# M502A.net
KiCad netlist of a schematic drawn in EAGLE
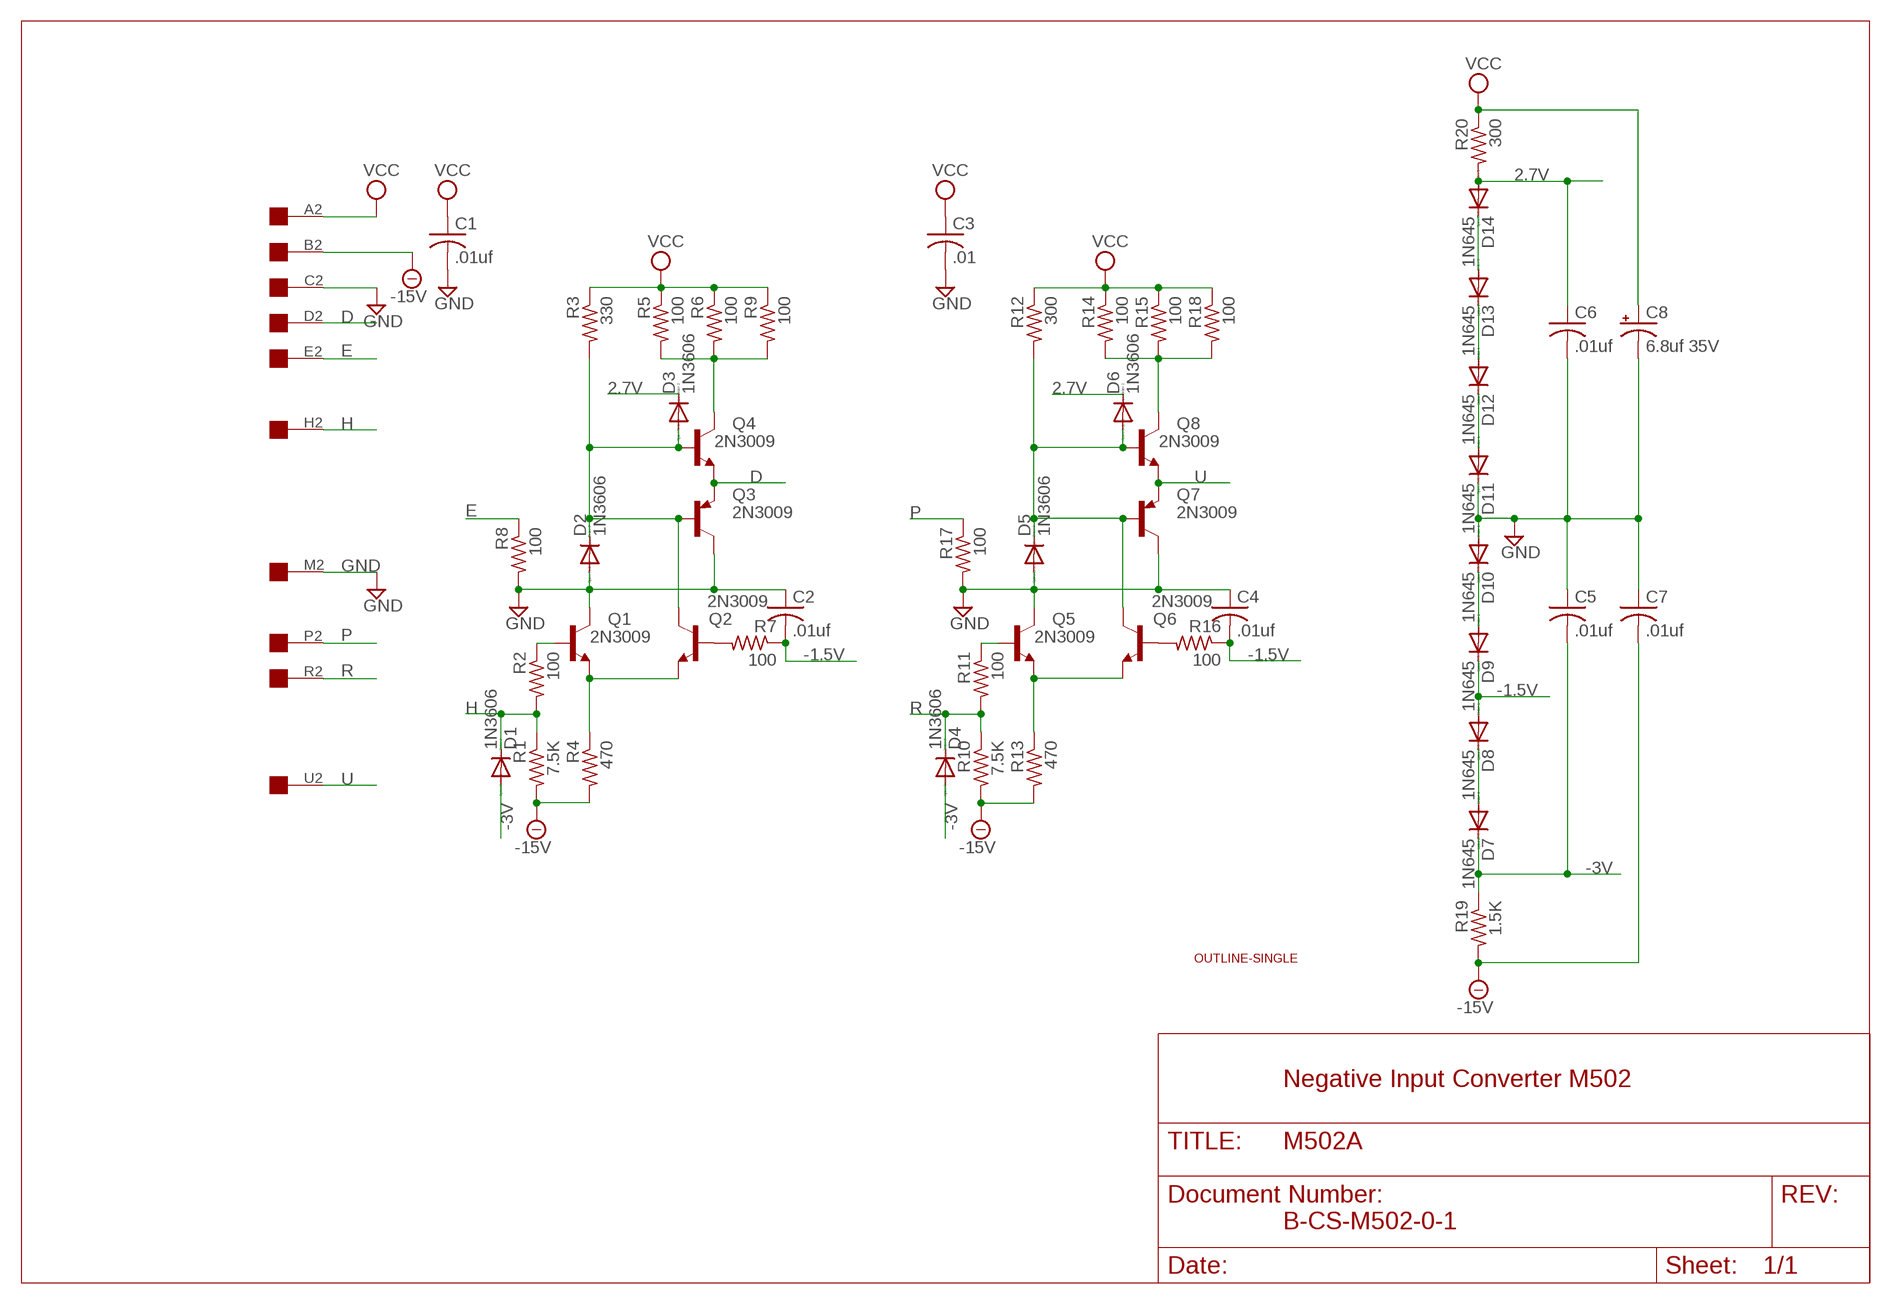
[diagram p0: schematic, sheet 1]

(export (version "E")
  (design (tool "Eeschema 10.0.6"))
  (components
    (comp (ref "C1")
      (value ".01uf")
      (footprint "eagle-import:C050-025X075")
      (libsource (lib "eagle-import") (part "C-US050-025X075"))
    )
    (comp (ref "C2")
      (value ".01uf")
      (footprint "eagle-import:C050-025X075")
      (libsource (lib "eagle-import") (part "C-US050-025X075"))
    )
    (comp (ref "C3")
      (value ".01")
      (footprint "eagle-import:C050-025X075")
      (libsource (lib "eagle-import") (part "C-US050-025X075"))
    )
    (comp (ref "C4")
      (value ".01uf")
      (footprint "eagle-import:C050-025X075")
      (libsource (lib "eagle-import") (part "C-US050-025X075"))
    )
    (comp (ref "C5")
      (value ".01uf")
      (footprint "eagle-import:C050-025X075")
      (libsource (lib "eagle-import") (part "C-US050-025X075"))
    )
    (comp (ref "C6")
      (value ".01uf")
      (footprint "eagle-import:C050-025X075")
      (libsource (lib "eagle-import") (part "C-US050-025X075"))
    )
    (comp (ref "C7")
      (value ".01uf")
      (footprint "eagle-import:C050-025X075")
      (libsource (lib "eagle-import") (part "C-US050-025X075"))
    )
    (comp (ref "C8")
      (value "6.8uf 35V")
      (footprint "eagle-import:E15-5")
      (libsource (lib "eagle-import") (part "CPOL-USE15-5AXIAL"))
    )
    (comp (ref "D1")
      (value "1N3606")
      (footprint "eagle-import:DO41-10")
      (libsource (lib "eagle-import") (part "1N4004"))
    )
    (comp (ref "D2")
      (value "1N3606")
      (footprint "eagle-import:DO41-10")
      (libsource (lib "eagle-import") (part "1N4004"))
    )
    (comp (ref "D3")
      (value "1N3606")
      (footprint "eagle-import:DO41-10")
      (libsource (lib "eagle-import") (part "1N4004"))
    )
    (comp (ref "D4")
      (value "1N3606")
      (footprint "eagle-import:DO41-10")
      (libsource (lib "eagle-import") (part "1N4004"))
    )
    (comp (ref "D5")
      (value "1N3606")
      (footprint "eagle-import:DO41-10")
      (libsource (lib "eagle-import") (part "1N4004"))
    )
    (comp (ref "D6")
      (value "1N3606")
      (footprint "eagle-import:DO41-10")
      (libsource (lib "eagle-import") (part "1N4004"))
    )
    (comp (ref "D7")
      (value "1N645")
      (footprint "eagle-import:DO41-10")
      (libsource (lib "eagle-import") (part "1N4004"))
    )
    (comp (ref "D8")
      (value "1N645")
      (footprint "eagle-import:DO41-10")
      (libsource (lib "eagle-import") (part "1N4004"))
    )
    (comp (ref "D9")
      (value "1N645")
      (footprint "eagle-import:DO41-10")
      (libsource (lib "eagle-import") (part "1N4004"))
    )
    (comp (ref "D10")
      (value "1N645")
      (footprint "eagle-import:DO41-10")
      (libsource (lib "eagle-import") (part "1N4004"))
    )
    (comp (ref "D11")
      (value "1N645")
      (footprint "eagle-import:DO41-10")
      (libsource (lib "eagle-import") (part "1N4004"))
    )
    (comp (ref "D12")
      (value "1N645")
      (footprint "eagle-import:DO41-10")
      (libsource (lib "eagle-import") (part "1N4004"))
    )
    (comp (ref "D13")
      (value "1N645")
      (footprint "eagle-import:DO41-10")
      (libsource (lib "eagle-import") (part "1N4004"))
    )
    (comp (ref "D14")
      (value "1N645")
      (footprint "eagle-import:DO41-10")
      (libsource (lib "eagle-import") (part "1N4004"))
    )
    (comp (ref "Q1")
      (value "2N3009")
      (footprint "eagle-import:TO39")
      (libsource (lib "eagle-import") (part "2N1711"))
    )
    (comp (ref "Q2")
      (value "2N3009")
      (footprint "eagle-import:TO39")
      (libsource (lib "eagle-import") (part "2N1711"))
    )
    (comp (ref "Q3")
      (value "2N3009")
      (footprint "eagle-import:TO39")
      (libsource (lib "eagle-import") (part "2N5415"))
    )
    (comp (ref "Q4")
      (value "2N3009")
      (footprint "eagle-import:TO39")
      (libsource (lib "eagle-import") (part "2N1711"))
    )
    (comp (ref "Q5")
      (value "2N3009")
      (footprint "eagle-import:TO39")
      (libsource (lib "eagle-import") (part "2N1711"))
    )
    (comp (ref "Q6")
      (value "2N3009")
      (footprint "eagle-import:TO39")
      (libsource (lib "eagle-import") (part "2N1711"))
    )
    (comp (ref "Q7")
      (value "2N3009")
      (footprint "eagle-import:TO39")
      (libsource (lib "eagle-import") (part "2N5415"))
    )
    (comp (ref "Q8")
      (value "2N3009")
      (footprint "eagle-import:TO39")
      (libsource (lib "eagle-import") (part "2N1711"))
    )
    (comp (ref "R1")
      (value "7.5K")
      (footprint "eagle-import:0207_10")
      (libsource (lib "eagle-import") (part "R-US_0207/10"))
    )
    (comp (ref "R2")
      (value "100")
      (footprint "eagle-import:0207_10")
      (libsource (lib "eagle-import") (part "R-US_0207/10"))
    )
    (comp (ref "R3")
      (value "330")
      (footprint "eagle-import:0207_10")
      (libsource (lib "eagle-import") (part "R-US_0207/10"))
    )
    (comp (ref "R4")
      (value "470")
      (footprint "eagle-import:0207_10")
      (libsource (lib "eagle-import") (part "R-US_0207/10"))
    )
    (comp (ref "R5")
      (value "100")
      (footprint "eagle-import:0207_10")
      (libsource (lib "eagle-import") (part "R-US_0207/10"))
    )
    (comp (ref "R6")
      (value "100")
      (footprint "eagle-import:0207_10")
      (libsource (lib "eagle-import") (part "R-US_0207/10"))
    )
    (comp (ref "R7")
      (value "100")
      (footprint "eagle-import:0207_10")
      (libsource (lib "eagle-import") (part "R-US_0207/10"))
    )
    (comp (ref "R8")
      (value "100")
      (footprint "eagle-import:0207_10")
      (libsource (lib "eagle-import") (part "R-US_0207/10"))
    )
    (comp (ref "R9")
      (value "100")
      (footprint "eagle-import:0207_10")
      (libsource (lib "eagle-import") (part "R-US_0207/10"))
    )
    (comp (ref "R10")
      (value "7.5K")
      (footprint "eagle-import:0207_10")
      (libsource (lib "eagle-import") (part "R-US_0207/10"))
    )
    (comp (ref "R11")
      (value "100")
      (footprint "eagle-import:0207_10")
      (libsource (lib "eagle-import") (part "R-US_0207/10"))
    )
    (comp (ref "R12")
      (value "300")
      (footprint "eagle-import:0207_10")
      (libsource (lib "eagle-import") (part "R-US_0207/10"))
    )
    (comp (ref "R13")
      (value "470")
      (footprint "eagle-import:0207_10")
      (libsource (lib "eagle-import") (part "R-US_0207/10"))
    )
    (comp (ref "R14")
      (value "100")
      (footprint "eagle-import:0207_10")
      (libsource (lib "eagle-import") (part "R-US_0207/10"))
    )
    (comp (ref "R15")
      (value "100")
      (footprint "eagle-import:0207_10")
      (libsource (lib "eagle-import") (part "R-US_0207/10"))
    )
    (comp (ref "R16")
      (value "100")
      (footprint "eagle-import:0207_10")
      (libsource (lib "eagle-import") (part "R-US_0207/10"))
    )
    (comp (ref "R17")
      (value "100")
      (footprint "eagle-import:0207_10")
      (libsource (lib "eagle-import") (part "R-US_0207/10"))
    )
    (comp (ref "R18")
      (value "100")
      (footprint "eagle-import:0207_10")
      (libsource (lib "eagle-import") (part "R-US_0207/10"))
    )
    (comp (ref "R19")
      (value "1.5K")
      (footprint "eagle-import:0207_10")
      (libsource (lib "eagle-import") (part "R-US_0207/10"))
    )
    (comp (ref "R20")
      (value "300")
      (footprint "eagle-import:0207_10")
      (libsource (lib "eagle-import") (part "R-US_0207/10"))
    )
    (comp (ref "U$1")
      (value "EDGE-1")
      (footprint "eagle-import:EDGE-CON1")
      (libsource (lib "eagle-import") (part "EDGE-1"))
    )
    (comp (ref "U$2")
      (value "OUTLINE-SINGLE")
      (footprint "eagle-import:SINGLE")
      (libsource (lib "eagle-import") (part "OUTLINE-SINGLE"))
    )
  )
  (nets
    (net (code "1") (name "-15V") (class "Default")
      (node (ref "C7") (pin "2") (pinfunction "2_2") (pintype "passive"))
      (node (ref "R1") (pin "2") (pinfunction "2_2") (pintype "passive"))
      (node (ref "R10") (pin "2") (pinfunction "2_2") (pintype "passive"))
      (node (ref "R13") (pin "2") (pinfunction "2_2") (pintype "passive"))
      (node (ref "R19") (pin "2") (pinfunction "2_2") (pintype "passive"))
      (node (ref "R4") (pin "2") (pinfunction "2_2") (pintype "passive"))
      (node (ref "U$1") (pin "B2") (pinfunction "1_B2") (pintype "bidirectional"))
    )
    (net (code "2") (name "/-1.5V") (class "Default")
      (node (ref "C2") (pin "2") (pinfunction "2_2") (pintype "passive"))
      (node (ref "C4") (pin "2") (pinfunction "2_2") (pintype "passive"))
      (node (ref "D8") (pin "A") (pinfunction "A_A") (pintype "passive"))
      (node (ref "D9") (pin "C") (pinfunction "C_C") (pintype "passive"))
      (node (ref "R16") (pin "1") (pinfunction "1_1") (pintype "passive"))
      (node (ref "R7") (pin "1") (pinfunction "1_1") (pintype "passive"))
    )
    (net (code "3") (name "/-3V") (class "Default")
      (node (ref "C5") (pin "2") (pinfunction "2_2") (pintype "passive"))
      (node (ref "D1") (pin "A") (pinfunction "A_A") (pintype "passive"))
      (node (ref "D4") (pin "A") (pinfunction "A_A") (pintype "passive"))
      (node (ref "D7") (pin "C") (pinfunction "C_C") (pintype "passive"))
      (node (ref "R19") (pin "1") (pinfunction "1_1") (pintype "passive"))
    )
    (net (code "4") (name "/2.7V") (class "Default")
      (node (ref "C6") (pin "1") (pinfunction "1_1") (pintype "passive"))
      (node (ref "D14") (pin "A") (pinfunction "A_A") (pintype "passive"))
      (node (ref "D3") (pin "C") (pinfunction "C_C") (pintype "passive"))
      (node (ref "D6") (pin "C") (pinfunction "C_C") (pintype "passive"))
      (node (ref "R20") (pin "2") (pinfunction "2_2") (pintype "passive"))
    )
    (net (code "5") (name "/D") (class "Default")
      (node (ref "Q3") (pin "1") (pinfunction "E_1") (pintype "passive"))
      (node (ref "Q4") (pin "1") (pinfunction "E_1") (pintype "passive"))
      (node (ref "U$1") (pin "D2") (pinfunction "1_D2") (pintype "bidirectional"))
    )
    (net (code "6") (name "/E") (class "Default")
      (node (ref "R8") (pin "1") (pinfunction "1_1") (pintype "passive"))
      (node (ref "U$1") (pin "E2") (pinfunction "1_E2") (pintype "bidirectional"))
    )
    (net (code "7") (name "/H") (class "Default")
      (node (ref "D1") (pin "C") (pinfunction "C_C") (pintype "passive"))
      (node (ref "R1") (pin "1") (pinfunction "1_1") (pintype "passive"))
      (node (ref "R2") (pin "2") (pinfunction "2_2") (pintype "passive"))
      (node (ref "U$1") (pin "H2") (pinfunction "1_H2") (pintype "bidirectional"))
    )
    (net (code "8") (name "/P") (class "Default")
      (node (ref "R17") (pin "1") (pinfunction "1_1") (pintype "passive"))
      (node (ref "U$1") (pin "P2") (pinfunction "1_P2") (pintype "bidirectional"))
    )
    (net (code "9") (name "/R") (class "Default")
      (node (ref "D4") (pin "C") (pinfunction "C_C") (pintype "passive"))
      (node (ref "R10") (pin "1") (pinfunction "1_1") (pintype "passive"))
      (node (ref "R11") (pin "2") (pinfunction "2_2") (pintype "passive"))
      (node (ref "U$1") (pin "R2") (pinfunction "1_R2") (pintype "bidirectional"))
    )
    (net (code "10") (name "/U") (class "Default")
      (node (ref "Q7") (pin "1") (pinfunction "E_1") (pintype "passive"))
      (node (ref "Q8") (pin "1") (pinfunction "E_1") (pintype "passive"))
      (node (ref "U$1") (pin "U2") (pinfunction "1_U2") (pintype "bidirectional"))
    )
    (net (code "11") (name "GND") (class "Default")
      (node (ref "C1") (pin "2") (pinfunction "2_2") (pintype "passive"))
      (node (ref "C2") (pin "1") (pinfunction "1_1") (pintype "passive"))
      (node (ref "C3") (pin "2") (pinfunction "2_2") (pintype "passive"))
      (node (ref "C4") (pin "1") (pinfunction "1_1") (pintype "passive"))
      (node (ref "C5") (pin "1") (pinfunction "1_1") (pintype "passive"))
      (node (ref "C6") (pin "2") (pinfunction "2_2") (pintype "passive"))
      (node (ref "C7") (pin "1") (pinfunction "1_1") (pintype "passive"))
      (node (ref "C8") (pin "-") (pinfunction "-_-") (pintype "passive"))
      (node (ref "D10") (pin "A") (pinfunction "A_A") (pintype "passive"))
      (node (ref "D11") (pin "C") (pinfunction "C_C") (pintype "passive"))
      (node (ref "D2") (pin "A") (pinfunction "A_A") (pintype "passive"))
      (node (ref "D5") (pin "A") (pinfunction "A_A") (pintype "passive"))
      (node (ref "Q1") (pin "3") (pinfunction "C_3") (pintype "passive"))
      (node (ref "Q3") (pin "3") (pinfunction "C_3") (pintype "passive"))
      (node (ref "Q5") (pin "3") (pinfunction "C_3") (pintype "passive"))
      (node (ref "Q7") (pin "3") (pinfunction "C_3") (pintype "passive"))
      (node (ref "R17") (pin "2") (pinfunction "2_2") (pintype "passive"))
      (node (ref "R8") (pin "2") (pinfunction "2_2") (pintype "passive"))
      (node (ref "U$1") (pin "C2") (pinfunction "1_C2") (pintype "bidirectional"))
      (node (ref "U$1") (pin "M2") (pinfunction "1_M2") (pintype "bidirectional"))
    )
    (net (code "12") (name "Net-(D7-PadA)") (class "Default")
      (node (ref "D7") (pin "A") (pinfunction "A_A") (pintype "passive"))
      (node (ref "D8") (pin "C") (pinfunction "C_C") (pintype "passive"))
    )
    (net (code "13") (name "Net-(D10-PadC)") (class "Default")
      (node (ref "D10") (pin "C") (pinfunction "C_C") (pintype "passive"))
      (node (ref "D9") (pin "A") (pinfunction "A_A") (pintype "passive"))
    )
    (net (code "14") (name "Net-(D11-PadA)") (class "Default")
      (node (ref "D11") (pin "A") (pinfunction "A_A") (pintype "passive"))
      (node (ref "D12") (pin "C") (pinfunction "C_C") (pintype "passive"))
    )
    (net (code "15") (name "Net-(D12-PadA)") (class "Default")
      (node (ref "D12") (pin "A") (pinfunction "A_A") (pintype "passive"))
      (node (ref "D13") (pin "C") (pinfunction "C_C") (pintype "passive"))
    )
    (net (code "16") (name "Net-(D13-PadA)") (class "Default")
      (node (ref "D13") (pin "A") (pinfunction "A_A") (pintype "passive"))
      (node (ref "D14") (pin "C") (pinfunction "C_C") (pintype "passive"))
    )
    (net (code "17") (name "Net-(Q1-B)") (class "Default")
      (node (ref "Q1") (pin "2") (pinfunction "B_2") (pintype "passive"))
      (node (ref "R2") (pin "1") (pinfunction "1_1") (pintype "passive"))
    )
    (net (code "18") (name "Net-(Q1-E)") (class "Default")
      (node (ref "Q1") (pin "1") (pinfunction "E_1") (pintype "passive"))
      (node (ref "Q2") (pin "1") (pinfunction "E_1") (pintype "passive"))
      (node (ref "R4") (pin "1") (pinfunction "1_1") (pintype "passive"))
    )
    (net (code "19") (name "Net-(Q2-B)") (class "Default")
      (node (ref "Q2") (pin "2") (pinfunction "B_2") (pintype "passive"))
      (node (ref "R7") (pin "2") (pinfunction "2_2") (pintype "passive"))
    )
    (net (code "20") (name "Net-(Q2-C)") (class "Default")
      (node (ref "D2") (pin "C") (pinfunction "C_C") (pintype "passive"))
      (node (ref "D3") (pin "A") (pinfunction "A_A") (pintype "passive"))
      (node (ref "Q2") (pin "3") (pinfunction "C_3") (pintype "passive"))
      (node (ref "Q3") (pin "2") (pinfunction "B_2") (pintype "passive"))
      (node (ref "Q4") (pin "2") (pinfunction "B_2") (pintype "passive"))
      (node (ref "R3") (pin "2") (pinfunction "2_2") (pintype "passive"))
    )
    (net (code "21") (name "Net-(Q4-C)") (class "Default")
      (node (ref "Q4") (pin "3") (pinfunction "C_3") (pintype "passive"))
      (node (ref "R5") (pin "2") (pinfunction "2_2") (pintype "passive"))
      (node (ref "R6") (pin "2") (pinfunction "2_2") (pintype "passive"))
      (node (ref "R9") (pin "2") (pinfunction "2_2") (pintype "passive"))
    )
    (net (code "22") (name "Net-(Q5-B)") (class "Default")
      (node (ref "Q5") (pin "2") (pinfunction "B_2") (pintype "passive"))
      (node (ref "R11") (pin "1") (pinfunction "1_1") (pintype "passive"))
    )
    (net (code "23") (name "Net-(Q5-E)") (class "Default")
      (node (ref "Q5") (pin "1") (pinfunction "E_1") (pintype "passive"))
      (node (ref "Q6") (pin "1") (pinfunction "E_1") (pintype "passive"))
      (node (ref "R13") (pin "1") (pinfunction "1_1") (pintype "passive"))
    )
    (net (code "24") (name "Net-(Q6-B)") (class "Default")
      (node (ref "Q6") (pin "2") (pinfunction "B_2") (pintype "passive"))
      (node (ref "R16") (pin "2") (pinfunction "2_2") (pintype "passive"))
    )
    (net (code "25") (name "Net-(Q6-C)") (class "Default")
      (node (ref "D5") (pin "C") (pinfunction "C_C") (pintype "passive"))
      (node (ref "D6") (pin "A") (pinfunction "A_A") (pintype "passive"))
      (node (ref "Q6") (pin "3") (pinfunction "C_3") (pintype "passive"))
      (node (ref "Q7") (pin "2") (pinfunction "B_2") (pintype "passive"))
      (node (ref "Q8") (pin "2") (pinfunction "B_2") (pintype "passive"))
      (node (ref "R12") (pin "2") (pinfunction "2_2") (pintype "passive"))
    )
    (net (code "26") (name "Net-(Q8-C)") (class "Default")
      (node (ref "Q8") (pin "3") (pinfunction "C_3") (pintype "passive"))
      (node (ref "R14") (pin "2") (pinfunction "2_2") (pintype "passive"))
      (node (ref "R15") (pin "2") (pinfunction "2_2") (pintype "passive"))
      (node (ref "R18") (pin "2") (pinfunction "2_2") (pintype "passive"))
    )
    (net (code "27") (name "VCC") (class "Default")
      (node (ref "C1") (pin "1") (pinfunction "1_1") (pintype "passive"))
      (node (ref "C3") (pin "1") (pinfunction "1_1") (pintype "passive"))
      (node (ref "C8") (pin "+") (pinfunction "+_+") (pintype "passive"))
      (node (ref "R12") (pin "1") (pinfunction "1_1") (pintype "passive"))
      (node (ref "R14") (pin "1") (pinfunction "1_1") (pintype "passive"))
      (node (ref "R15") (pin "1") (pinfunction "1_1") (pintype "passive"))
      (node (ref "R18") (pin "1") (pinfunction "1_1") (pintype "passive"))
      (node (ref "R20") (pin "1") (pinfunction "1_1") (pintype "passive"))
      (node (ref "R3") (pin "1") (pinfunction "1_1") (pintype "passive"))
      (node (ref "R5") (pin "1") (pinfunction "1_1") (pintype "passive"))
      (node (ref "R6") (pin "1") (pinfunction "1_1") (pintype "passive"))
      (node (ref "R9") (pin "1") (pinfunction "1_1") (pintype "passive"))
      (node (ref "U$1") (pin "A2") (pinfunction "1_A2") (pintype "bidirectional"))
    )
  )
)
